# DS18B20Modular1B.net
KiCad netlist of a schematic drawn in EAGLE
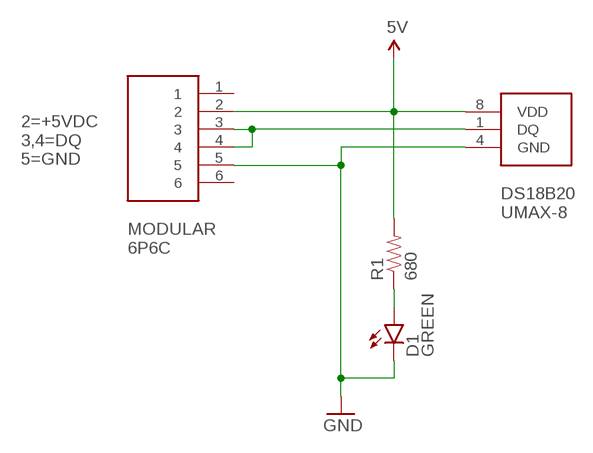
[diagram p0: schematic, sheet 1]

(export (version "E")
  (design (tool "Eeschema 10.0.6"))
  (components
    (comp (ref "D1")
      (value "GREEN")
      (footprint "eagle-import:LED-0603")
      (libsource (lib "eagle-import") (part "LED-GREEN0603"))
    )
    (comp (ref "J1")
      (value "MODULAR-JACK-6P6C-1")
      (footprint "eagle-import:MODULAR-JACK-6P6C-1")
      (libsource (lib "eagle-import") (part "MODULAR-JACK-6P6C-1"))
    )
    (comp (ref "R1")
      (value "680")
      (footprint "eagle-import:0805")
      (libsource (lib "eagle-import") (part "RES-680-0805"))
    )
    (comp (ref "U$1")
      (value "DS18B20UMAX-8")
      (footprint "eagle-import:UMAX-8-MAXIM")
      (libsource (lib "eagle-import") (part "DS18B20UMAX-8"))
    )
  )
  (nets
    (net (code "1") (name "5V") (class "Default")
      (node (ref "J1") (pin "2") (pinfunction "2_2") (pintype "passive"))
      (node (ref "R1") (pin "2") (pinfunction "2_2") (pintype "passive"))
      (node (ref "U$1") (pin "8") (pinfunction "VDD_8") (pintype "power_in"))
    )
    (net (code "2") (name "GND") (class "Default")
      (node (ref "D1") (pin "C") (pinfunction "C_C") (pintype "passive"))
      (node (ref "J1") (pin "5") (pinfunction "5_5") (pintype "passive"))
      (node (ref "U$1") (pin "4") (pinfunction "GND_4") (pintype "power_in"))
    )
    (net (code "3") (name "Net-(D1-PadA)") (class "Default")
      (node (ref "D1") (pin "A") (pinfunction "A_A") (pintype "passive"))
      (node (ref "R1") (pin "1") (pinfunction "1_1") (pintype "passive"))
    )
    (net (code "4") (name "Net-(U$1-DQ)") (class "Default")
      (node (ref "J1") (pin "3") (pinfunction "3_3") (pintype "passive"))
      (node (ref "J1") (pin "4") (pinfunction "4_4") (pintype "passive"))
      (node (ref "U$1") (pin "1") (pinfunction "DQ_1") (pintype "bidirectional"))
    )
    (net (code "5") (name "unconnected-(J1-Pad1)") (class "Default")
      (node (ref "J1") (pin "1") (pinfunction "1_1") (pintype "passive"))
    )
    (net (code "6") (name "unconnected-(J1-Pad6)") (class "Default")
      (node (ref "J1") (pin "6") (pinfunction "6_6") (pintype "passive"))
    )
  )
)
